# Test1.net
KiCad netlist of a schematic drawn in Altium Designer
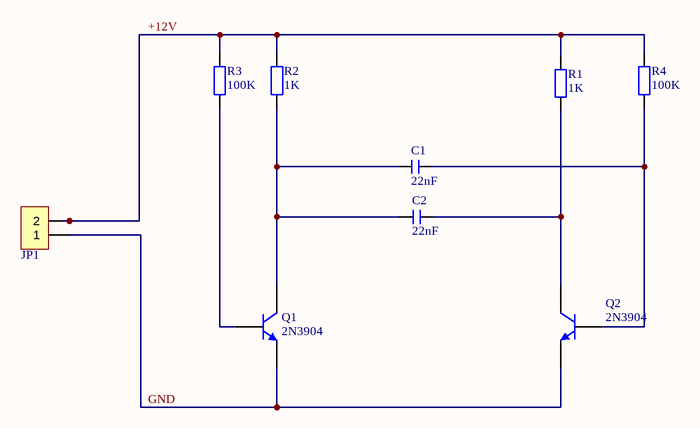
[diagram p0: Test1.SchDoc]

(export (version "E")
  (design (tool "Eeschema 10.0.6"))
  (components
    (comp (ref "C1")
      (value "22nF")
      (footprint "C 0603_L")
      (description "无极性贴片电容")
      (fields (field (name "版权归属") "源创客"))
      (libsource (lib "3.1   - 电阻-电容-电感") (part "C"))
    )
    (comp (ref "C2")
      (value "22nF")
      (footprint "C 0603_L")
      (description "无极性贴片电容")
      (fields (field (name "版权归属") "源创客"))
      (libsource (lib "3.1   - 电阻-电容-电感") (part "C"))
    )
    (comp (ref "JP1")
      (value "HDR-1X2")
      (footprint "HDR2.54-LI-2P")
      (description "2P接插件")
      (fields (field (name "版权归属") "源创客"))
      (libsource (lib "4.2   - 接插件-脚距1.25") (part "Header 2"))
    )
    (comp (ref "Q1")
      (value "2N3904")
      (footprint "TO-92A")
      (description "NPN General Purpose Amplifier")
      (fields (field (name "PUBLISHER") "Altium Limited"))
      (libsource (lib "Miscellaneous Devices") (part "2N3904"))
    )
    (comp (ref "Q2")
      (value "2N3904")
      (footprint "TO-92A")
      (description "NPN General Purpose Amplifier")
      (fields (field (name "PUBLISHER") "Altium Limited"))
      (libsource (lib "Miscellaneous Devices") (part "2N3904"))
    )
    (comp (ref "R1")
      (value "1K")
      (footprint "电阻贴片:0805R")
      (description "贴片电阻")
      (fields (field (name "版权归属") "源创客"))
      (libsource (lib "3.1   - 电阻-电容-电感") (part "R"))
    )
    (comp (ref "R2")
      (value "1K")
      (footprint "电阻贴片:0805R")
      (description "贴片电阻")
      (fields (field (name "版权归属") "源创客"))
      (libsource (lib "3.1   - 电阻-电容-电感") (part "R"))
    )
    (comp (ref "R3")
      (value "100K")
      (footprint "电阻贴片:0805R")
      (description "贴片电阻")
      (fields (field (name "版权归属") "源创客"))
      (libsource (lib "3.1   - 电阻-电容-电感") (part "R"))
    )
    (comp (ref "R4")
      (value "100K")
      (footprint "电阻贴片:0805R")
      (description "贴片电阻")
      (fields (field (name "版权归属") "源创客"))
      (libsource (lib "3.1   - 电阻-电容-电感") (part "R"))
    )
  )
  (nets
    (net (code "1") (name "/+12V") (class "Default")
      (node (ref "JP1") (pin "2") (pinfunction "2_2") (pintype "passive"))
      (node (ref "R1") (pin "2") (pinfunction "2_2") (pintype "passive"))
      (node (ref "R2") (pin "2") (pinfunction "2_2") (pintype "passive"))
      (node (ref "R3") (pin "2") (pinfunction "2_2") (pintype "passive"))
      (node (ref "R4") (pin "2") (pinfunction "2_2") (pintype "passive"))
    )
    (net (code "2") (name "/GND") (class "Default")
      (node (ref "JP1") (pin "1") (pinfunction "1_1") (pintype "passive"))
      (node (ref "Q1") (pin "1") (pinfunction "E_1") (pintype "passive"))
      (node (ref "Q2") (pin "1") (pinfunction "E_1") (pintype "passive"))
    )
    (net (code "3") (name "Net-(Q1-B)") (class "Default")
      (node (ref "Q1") (pin "2") (pinfunction "B_2") (pintype "passive"))
      (node (ref "R3") (pin "1") (pinfunction "1_1") (pintype "passive"))
    )
    (net (code "4") (name "Net-(Q1-C)") (class "Default")
      (node (ref "C1") (pin "1") (pinfunction "1_1") (pintype "passive"))
      (node (ref "C2") (pin "1") (pinfunction "1_1") (pintype "passive"))
      (node (ref "Q1") (pin "3") (pinfunction "C_3") (pintype "passive"))
      (node (ref "R2") (pin "1") (pinfunction "1_1") (pintype "passive"))
    )
    (net (code "5") (name "Net-(Q2-B)") (class "Default")
      (node (ref "C1") (pin "2") (pinfunction "2_2") (pintype "passive"))
      (node (ref "Q2") (pin "2") (pinfunction "B_2") (pintype "passive"))
      (node (ref "R4") (pin "1") (pinfunction "1_1") (pintype "passive"))
    )
    (net (code "6") (name "Net-(Q2-C)") (class "Default")
      (node (ref "C2") (pin "2") (pinfunction "2_2") (pintype "passive"))
      (node (ref "Q2") (pin "3") (pinfunction "C_3") (pintype "passive"))
      (node (ref "R1") (pin "1") (pinfunction "1_1") (pintype "passive"))
    )
  )
)
